# ATS.net
KiCad netlist of a schematic drawn in EAGLE
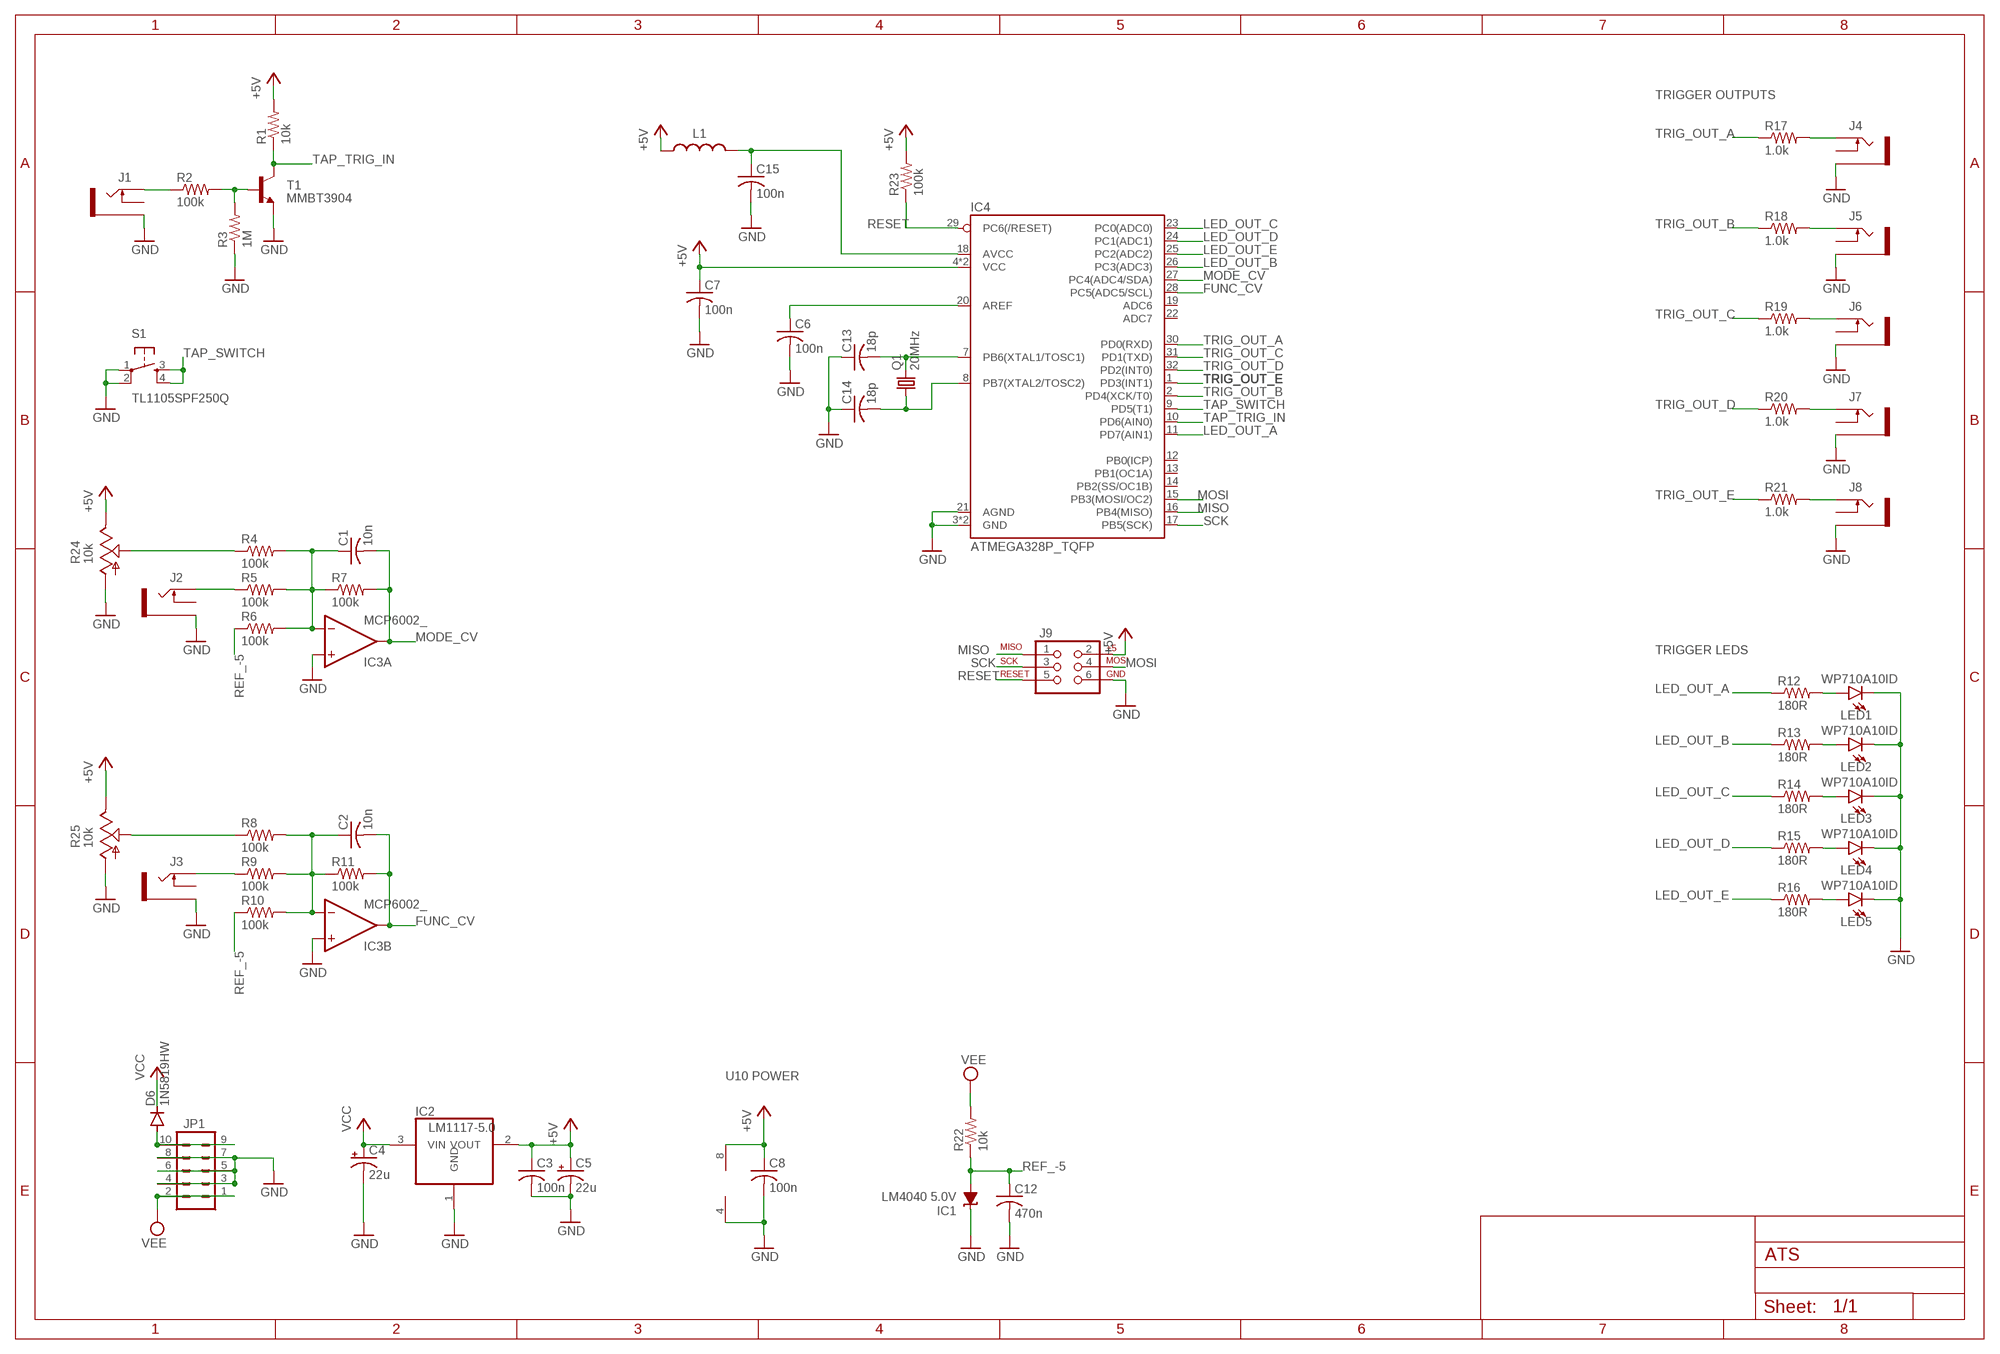
[diagram p0: schematic, sheet 1]

(export (version "E")
  (design (tool "Eeschema 10.0.6"))
  (components
    (comp (ref "C1")
      (value "10n")
      (footprint "eagle-import:C0603")
      (libsource (lib "eagle-import") (part "C-USC0603"))
    )
    (comp (ref "C2")
      (value "10n")
      (footprint "eagle-import:C0603")
      (libsource (lib "eagle-import") (part "C-USC0603"))
    )
    (comp (ref "C3")
      (value "100n")
      (footprint "eagle-import:C0603")
      (libsource (lib "eagle-import") (part "C-USC0603"))
    )
    (comp (ref "C4")
      (value "22u")
      (footprint "eagle-import:PANASONIC_C")
      (libsource (lib "eagle-import") (part "CPOL-USC"))
    )
    (comp (ref "C5")
      (value "22u")
      (footprint "eagle-import:PANASONIC_C")
      (libsource (lib "eagle-import") (part "CPOL-USC"))
    )
    (comp (ref "C6")
      (value "100n")
      (footprint "eagle-import:C0603")
      (libsource (lib "eagle-import") (part "C-USC0603"))
    )
    (comp (ref "C7")
      (value "100n")
      (footprint "eagle-import:C0603")
      (libsource (lib "eagle-import") (part "C-USC0603"))
    )
    (comp (ref "C8")
      (value "100n")
      (footprint "eagle-import:C0603")
      (libsource (lib "eagle-import") (part "C-USC0603"))
    )
    (comp (ref "C12")
      (value "470n")
      (footprint "eagle-import:C0603")
      (libsource (lib "eagle-import") (part "C-USC0603"))
    )
    (comp (ref "C13")
      (value "18p")
      (footprint "eagle-import:C0603")
      (libsource (lib "eagle-import") (part "C-USC0603"))
    )
    (comp (ref "C14")
      (value "18p")
      (footprint "eagle-import:C0603")
      (libsource (lib "eagle-import") (part "C-USC0603"))
    )
    (comp (ref "C15")
      (value "100n")
      (footprint "eagle-import:C0603")
      (libsource (lib "eagle-import") (part "C-USC0603"))
    )
    (comp (ref "D6")
      (value "1N5819HW")
      (footprint "eagle-import:SOD123")
      (libsource (lib "eagle-import") (part "DIODE-SOD123"))
    )
    (comp (ref "IC1")
      (value "LM4040 5.0V")
      (footprint "eagle-import:DBZ_R-PDSO-G3")
      (fields (field (name "MF") "TEXAS INSTRUMENT CONNECTORS") (field (name "MPN") "LM4041C12QDBZT"))
      (libsource (lib "eagle-import") (part "LM4041DBZC12"))
    )
    (comp (ref "IC2")
      (value "LM1117-5.0")
      (footprint "eagle-import:SOT223")
      (fields (field (name "MPN") "REG1117"))
      (libsource (lib "eagle-import") (part "REG1117"))
    )
    (comp (ref "IC3")
      (value "MCP6002_")
      (footprint "eagle-import:SO08")
      (libsource (lib "eagle-import") (part "MCP6002_"))
    )
    (comp (ref "IC4")
      (value "ATMEGA328P_TQFP")
      (footprint "eagle-import:TQFP32-08")
      (libsource (lib "eagle-import") (part "ATMEGA328P_TQFP"))
    )
    (comp (ref "J1")
      (value "THONKICONNNEW")
      (footprint "eagle-import:WQP-PJ301M-12_JACK")
      (libsource (lib "eagle-import") (part "THONKICONNNEW"))
    )
    (comp (ref "J2")
      (value "THONKICONNNEW")
      (footprint "eagle-import:WQP-PJ301M-12_JACK")
      (libsource (lib "eagle-import") (part "THONKICONNNEW"))
    )
    (comp (ref "J3")
      (value "THONKICONNNEW")
      (footprint "eagle-import:WQP-PJ301M-12_JACK")
      (libsource (lib "eagle-import") (part "THONKICONNNEW"))
    )
    (comp (ref "J4")
      (value "THONKICONNNEW")
      (footprint "eagle-import:WQP-PJ301M-12_JACK")
      (libsource (lib "eagle-import") (part "THONKICONNNEW"))
    )
    (comp (ref "J5")
      (value "THONKICONNNEW")
      (footprint "eagle-import:WQP-PJ301M-12_JACK")
      (libsource (lib "eagle-import") (part "THONKICONNNEW"))
    )
    (comp (ref "J6")
      (value "THONKICONNNEW")
      (footprint "eagle-import:WQP-PJ301M-12_JACK")
      (libsource (lib "eagle-import") (part "THONKICONNNEW"))
    )
    (comp (ref "J7")
      (value "THONKICONNNEW")
      (footprint "eagle-import:WQP-PJ301M-12_JACK")
      (libsource (lib "eagle-import") (part "THONKICONNNEW"))
    )
    (comp (ref "J8")
      (value "THONKICONNNEW")
      (footprint "eagle-import:WQP-PJ301M-12_JACK")
      (libsource (lib "eagle-import") (part "THONKICONNNEW"))
    )
    (comp (ref "J9")
      (value "AVR_SPI_PRG_6PTH")
      (footprint "eagle-import:2X3")
      (libsource (lib "eagle-import") (part "AVR_SPI_PRG_6PTH"))
    )
    (comp (ref "JP1")
      (value "EURO_POWER_HEADERREGULAR")
      (footprint "eagle-import:EURO_POWER_HEADER")
      (libsource (lib "eagle-import") (part "EURO_POWER_HEADERREGULAR"))
    )
    (comp (ref "L1")
      (value "470Ohm@100MHz")
      (footprint "eagle-import:WE-CBF_0603(W=2.2)")
      (libsource (lib "eagle-import") (part "WE-CBF_0603_WB_HS_742792642"))
    )
    (comp (ref "LED1")
      (value "WP710A10ID")
      (footprint "eagle-import:LED_3MM")
      (fields (field (name "SPICEPREFIX") "D"))
      (libsource (lib "eagle-import") (part "LED3MM"))
    )
    (comp (ref "LED2")
      (value "WP710A10ID")
      (footprint "eagle-import:LED_3MM")
      (libsource (lib "eagle-import") (part "LED3MM"))
    )
    (comp (ref "LED3")
      (value "WP710A10ID")
      (footprint "eagle-import:LED_3MM")
      (libsource (lib "eagle-import") (part "LED3MM"))
    )
    (comp (ref "LED4")
      (value "WP710A10ID")
      (footprint "eagle-import:LED_3MM")
      (libsource (lib "eagle-import") (part "LED3MM"))
    )
    (comp (ref "LED5")
      (value "WP710A10ID")
      (footprint "eagle-import:LED_3MM")
      (libsource (lib "eagle-import") (part "LED3MM"))
    )
    (comp (ref "Q1")
      (value "20MHz")
      (footprint "eagle-import:HC49UP")
      (libsource (lib "eagle-import") (part "CRYSTALHC49UP"))
    )
    (comp (ref "R1")
      (value "10k")
      (footprint "eagle-import:R0603")
      (libsource (lib "eagle-import") (part "R-US_R0603"))
    )
    (comp (ref "R2")
      (value "100k")
      (footprint "eagle-import:R0603")
      (libsource (lib "eagle-import") (part "R-US_R0603"))
    )
    (comp (ref "R3")
      (value "1M")
      (footprint "eagle-import:R0603")
      (libsource (lib "eagle-import") (part "R-US_R0603"))
    )
    (comp (ref "R4")
      (value "100k")
      (footprint "eagle-import:R0603")
      (libsource (lib "eagle-import") (part "R-US_R0603"))
    )
    (comp (ref "R5")
      (value "100k")
      (footprint "eagle-import:R0603")
      (libsource (lib "eagle-import") (part "R-US_R0603"))
    )
    (comp (ref "R6")
      (value "100k")
      (footprint "eagle-import:R0603")
      (libsource (lib "eagle-import") (part "R-US_R0603"))
    )
    (comp (ref "R7")
      (value "100k")
      (footprint "eagle-import:R0603")
      (libsource (lib "eagle-import") (part "R-US_R0603"))
    )
    (comp (ref "R8")
      (value "100k")
      (footprint "eagle-import:R0603")
      (libsource (lib "eagle-import") (part "R-US_R0603"))
    )
    (comp (ref "R9")
      (value "100k")
      (footprint "eagle-import:R0603")
      (libsource (lib "eagle-import") (part "R-US_R0603"))
    )
    (comp (ref "R10")
      (value "100k")
      (footprint "eagle-import:R0603")
      (libsource (lib "eagle-import") (part "R-US_R0603"))
    )
    (comp (ref "R11")
      (value "100k")
      (footprint "eagle-import:R0603")
      (libsource (lib "eagle-import") (part "R-US_R0603"))
    )
    (comp (ref "R12")
      (value "180R")
      (footprint "eagle-import:R0603")
      (libsource (lib "eagle-import") (part "R-US_R0603"))
    )
    (comp (ref "R13")
      (value "180R")
      (footprint "eagle-import:R0603")
      (libsource (lib "eagle-import") (part "R-US_R0603"))
    )
    (comp (ref "R14")
      (value "180R")
      (footprint "eagle-import:R0603")
      (libsource (lib "eagle-import") (part "R-US_R0603"))
    )
    (comp (ref "R15")
      (value "180R")
      (footprint "eagle-import:R0603")
      (libsource (lib "eagle-import") (part "R-US_R0603"))
    )
    (comp (ref "R16")
      (value "180R")
      (footprint "eagle-import:R0603")
      (libsource (lib "eagle-import") (part "R-US_R0603"))
    )
    (comp (ref "R17")
      (value "1.0k")
      (footprint "eagle-import:R0603")
      (libsource (lib "eagle-import") (part "R-US_R0603"))
    )
    (comp (ref "R18")
      (value "1.0k")
      (footprint "eagle-import:R0603")
      (libsource (lib "eagle-import") (part "R-US_R0603"))
    )
    (comp (ref "R19")
      (value "1.0k")
      (footprint "eagle-import:R0603")
      (libsource (lib "eagle-import") (part "R-US_R0603"))
    )
    (comp (ref "R20")
      (value "1.0k")
      (footprint "eagle-import:R0603")
      (libsource (lib "eagle-import") (part "R-US_R0603"))
    )
    (comp (ref "R21")
      (value "1.0k")
      (footprint "eagle-import:R0603")
      (libsource (lib "eagle-import") (part "R-US_R0603"))
    )
    (comp (ref "R22")
      (value "10k")
      (footprint "eagle-import:R0603")
      (libsource (lib "eagle-import") (part "R-US_R0603"))
    )
    (comp (ref "R23")
      (value "100k")
      (footprint "eagle-import:R0603")
      (libsource (lib "eagle-import") (part "R-US_R0603"))
    )
    (comp (ref "R24")
      (value "10k")
      (footprint "eagle-import:9MM_SNAP-IN_POT")
      (libsource (lib "eagle-import") (part "9MM_SNAP-IN_POT_"))
    )
    (comp (ref "R25")
      (value "10k")
      (footprint "eagle-import:9MM_SNAP-IN_POT")
      (libsource (lib "eagle-import") (part "9MM_SNAP-IN_POT_"))
    )
    (comp (ref "S1")
      (value "TL1105SPF250Q")
      (footprint "eagle-import:TACTILE-PTH")
      (libsource (lib "eagle-import") (part "TAC_SWITCHPTH"))
    )
    (comp (ref "T1")
      (value "MMBT3904")
      (footprint "eagle-import:SOT23-BEC")
      (libsource (lib "eagle-import") (part "-NPN-SOT23-BECMMBT3904LT1"))
    )
  )
  (nets
    (net (code "1") (name "+5V") (class "Default")
      (node (ref "C3") (pin "1") (pinfunction "1_1") (pintype "passive"))
      (node (ref "C5") (pin "+") (pinfunction "+_+") (pintype "passive"))
      (node (ref "C7") (pin "1") (pinfunction "1_1") (pintype "passive"))
      (node (ref "C8") (pin "1") (pinfunction "1_1") (pintype "passive"))
      (node (ref "IC2") (pin "2") (pinfunction "VOUT_2") (pintype "output"))
      (node (ref "IC3") (pin "8") (pinfunction "V+_8") (pintype "power_in"))
      (node (ref "IC4") (pin "4") (pinfunction "VCC_4") (pintype "bidirectional"))
      (node (ref "IC4") (pin "6") (pinfunction "VCC_6") (pintype "bidirectional"))
      (node (ref "J9") (pin "2") (pinfunction "2_2") (pintype "passive"))
      (node (ref "L1") (pin "1") (pinfunction "1_1") (pintype "passive"))
      (node (ref "R1") (pin "2") (pinfunction "2_2") (pintype "passive"))
      (node (ref "R23") (pin "2") (pinfunction "2_2") (pintype "passive"))
      (node (ref "R24") (pin "3") (pinfunction "E_3") (pintype "passive"))
      (node (ref "R25") (pin "3") (pinfunction "E_3") (pintype "passive"))
    )
    (net (code "2") (name "/FUNC_CV") (class "Default")
      (node (ref "C2") (pin "2") (pinfunction "2_2") (pintype "passive"))
      (node (ref "IC3") (pin "7") (pinfunction "OUT_7") (pintype "output"))
      (node (ref "IC4") (pin "28") (pinfunction "PC5(ADC5/SCL)_28") (pintype "bidirectional"))
      (node (ref "R11") (pin "2") (pinfunction "2_2") (pintype "passive"))
    )
    (net (code "3") (name "/LED_OUT_A") (class "Default")
      (node (ref "IC4") (pin "11") (pinfunction "PD7(AIN1)_11") (pintype "bidirectional"))
      (node (ref "R12") (pin "1") (pinfunction "1_1") (pintype "passive"))
    )
    (net (code "4") (name "/LED_OUT_B") (class "Default")
      (node (ref "IC4") (pin "26") (pinfunction "PC3(ADC3)_26") (pintype "bidirectional"))
      (node (ref "R13") (pin "1") (pinfunction "1_1") (pintype "passive"))
    )
    (net (code "5") (name "/LED_OUT_C") (class "Default")
      (node (ref "IC4") (pin "23") (pinfunction "PC0(ADC0)_23") (pintype "bidirectional"))
      (node (ref "R14") (pin "1") (pinfunction "1_1") (pintype "passive"))
    )
    (net (code "6") (name "/LED_OUT_D") (class "Default")
      (node (ref "IC4") (pin "24") (pinfunction "PC1(ADC1)_24") (pintype "bidirectional"))
      (node (ref "R15") (pin "1") (pinfunction "1_1") (pintype "passive"))
    )
    (net (code "7") (name "/LED_OUT_E") (class "Default")
      (node (ref "IC4") (pin "25") (pinfunction "PC2(ADC2)_25") (pintype "bidirectional"))
      (node (ref "R16") (pin "1") (pinfunction "1_1") (pintype "passive"))
    )
    (net (code "8") (name "/MISO") (class "Default")
      (node (ref "IC4") (pin "16") (pinfunction "PB4(MISO)_16") (pintype "bidirectional"))
      (node (ref "J9") (pin "1") (pinfunction "1_1") (pintype "passive"))
    )
    (net (code "9") (name "/MODE_CV") (class "Default")
      (node (ref "C1") (pin "2") (pinfunction "2_2") (pintype "passive"))
      (node (ref "IC3") (pin "1") (pinfunction "OUT_1") (pintype "output"))
      (node (ref "IC4") (pin "27") (pinfunction "PC4(ADC4/SDA)_27") (pintype "bidirectional"))
      (node (ref "R7") (pin "2") (pinfunction "2_2") (pintype "passive"))
    )
    (net (code "10") (name "/MOSI") (class "Default")
      (node (ref "IC4") (pin "15") (pinfunction "PB3(MOSI/OC2)_15") (pintype "bidirectional"))
      (node (ref "J9") (pin "4") (pinfunction "4_4") (pintype "passive"))
    )
    (net (code "11") (name "/REF_-5") (class "Default")
      (node (ref "C12") (pin "1") (pinfunction "1_1") (pintype "passive"))
      (node (ref "IC1") (pin "2") (pinfunction "A_2") (pintype "passive"))
      (node (ref "R10") (pin "1") (pinfunction "1_1") (pintype "passive"))
      (node (ref "R22") (pin "1") (pinfunction "1_1") (pintype "passive"))
      (node (ref "R6") (pin "1") (pinfunction "1_1") (pintype "passive"))
    )
    (net (code "12") (name "/RESET") (class "Default")
      (node (ref "IC4") (pin "29") (pinfunction "PC6(/RESET)_29") (pintype "bidirectional"))
      (node (ref "J9") (pin "5") (pinfunction "5_5") (pintype "passive"))
      (node (ref "R23") (pin "1") (pinfunction "1_1") (pintype "passive"))
    )
    (net (code "13") (name "/SCK") (class "Default")
      (node (ref "IC4") (pin "17") (pinfunction "PB5(SCK)_17") (pintype "bidirectional"))
      (node (ref "J9") (pin "3") (pinfunction "3_3") (pintype "passive"))
    )
    (net (code "14") (name "/TAP_SWITCH") (class "Default")
      (node (ref "IC4") (pin "9") (pinfunction "PD5(T1)_9") (pintype "bidirectional"))
      (node (ref "S1") (pin "3") (pinfunction "3_3") (pintype "passive"))
      (node (ref "S1") (pin "4") (pinfunction "4_4") (pintype "passive"))
    )
    (net (code "15") (name "/TAP_TRIG_IN") (class "Default")
      (node (ref "IC4") (pin "10") (pinfunction "PD6(AIN0)_10") (pintype "bidirectional"))
      (node (ref "R1") (pin "1") (pinfunction "1_1") (pintype "passive"))
      (node (ref "T1") (pin "C") (pinfunction "C_C") (pintype "passive"))
    )
    (net (code "16") (name "/TRIG_OUT_A") (class "Default")
      (node (ref "IC4") (pin "30") (pinfunction "PD0(RXD)_30") (pintype "bidirectional"))
      (node (ref "R17") (pin "1") (pinfunction "1_1") (pintype "passive"))
    )
    (net (code "17") (name "/TRIG_OUT_B") (class "Default")
      (node (ref "IC4") (pin "2") (pinfunction "PD4(XCK/T0)_2") (pintype "bidirectional"))
      (node (ref "R18") (pin "1") (pinfunction "1_1") (pintype "passive"))
    )
    (net (code "18") (name "/TRIG_OUT_C") (class "Default")
      (node (ref "IC4") (pin "31") (pinfunction "PD1(TXD)_31") (pintype "bidirectional"))
      (node (ref "R19") (pin "1") (pinfunction "1_1") (pintype "passive"))
    )
    (net (code "19") (name "/TRIG_OUT_D") (class "Default")
      (node (ref "IC4") (pin "32") (pinfunction "PD2(INT0)_32") (pintype "bidirectional"))
      (node (ref "R20") (pin "1") (pinfunction "1_1") (pintype "passive"))
    )
    (net (code "20") (name "/TRIG_OUT_E") (class "Default")
      (node (ref "IC4") (pin "1") (pinfunction "PD3(INT1)_1") (pintype "bidirectional"))
      (node (ref "R21") (pin "1") (pinfunction "1_1") (pintype "passive"))
    )
    (net (code "21") (name "GND") (class "Default")
      (node (ref "C12") (pin "2") (pinfunction "2_2") (pintype "passive"))
      (node (ref "C13") (pin "1") (pinfunction "1_1") (pintype "passive"))
      (node (ref "C14") (pin "1") (pinfunction "1_1") (pintype "passive"))
      (node (ref "C15") (pin "2") (pinfunction "2_2") (pintype "passive"))
      (node (ref "C3") (pin "2") (pinfunction "2_2") (pintype "passive"))
      (node (ref "C4") (pin "-") (pinfunction "-_-") (pintype "passive"))
      (node (ref "C5") (pin "-") (pinfunction "-_-") (pintype "passive"))
      (node (ref "C6") (pin "2") (pinfunction "2_2") (pintype "passive"))
      (node (ref "C7") (pin "2") (pinfunction "2_2") (pintype "passive"))
      (node (ref "C8") (pin "2") (pinfunction "2_2") (pintype "passive"))
      (node (ref "IC1") (pin "1") (pinfunction "C_1") (pintype "passive"))
      (node (ref "IC2") (pin "1") (pinfunction "GND_1") (pintype "power_in"))
      (node (ref "IC3") (pin "3") (pinfunction "+IN_3") (pintype "input"))
      (node (ref "IC3") (pin "4") (pinfunction "V-_4") (pintype "power_in"))
      (node (ref "IC3") (pin "5") (pinfunction "+IN_5") (pintype "input"))
      (node (ref "IC4") (pin "21") (pinfunction "AGND_21") (pintype "bidirectional"))
      (node (ref "IC4") (pin "3") (pinfunction "GND_3") (pintype "bidirectional"))
      (node (ref "IC4") (pin "5") (pinfunction "GND_5") (pintype "bidirectional"))
      (node (ref "J1") (pin "P$3_SLEEVE") (pinfunction "SLEEVE_P$3_SLEEVE") (pintype "passive"))
      (node (ref "J2") (pin "P$3_SLEEVE") (pinfunction "SLEEVE_P$3_SLEEVE") (pintype "passive"))
      (node (ref "J3") (pin "P$3_SLEEVE") (pinfunction "SLEEVE_P$3_SLEEVE") (pintype "passive"))
      (node (ref "J4") (pin "P$3_SLEEVE") (pinfunction "SLEEVE_P$3_SLEEVE") (pintype "passive"))
      (node (ref "J5") (pin "P$3_SLEEVE") (pinfunction "SLEEVE_P$3_SLEEVE") (pintype "passive"))
      (node (ref "J6") (pin "P$3_SLEEVE") (pinfunction "SLEEVE_P$3_SLEEVE") (pintype "passive"))
      (node (ref "J7") (pin "P$3_SLEEVE") (pinfunction "SLEEVE_P$3_SLEEVE") (pintype "passive"))
      (node (ref "J8") (pin "P$3_SLEEVE") (pinfunction "SLEEVE_P$3_SLEEVE") (pintype "passive"))
      (node (ref "J9") (pin "6") (pinfunction "6_6") (pintype "passive"))
      (node (ref "JP1") (pin "3") (pinfunction "3_3") (pintype "passive"))
      (node (ref "JP1") (pin "4") (pinfunction "4_4") (pintype "passive"))
      (node (ref "JP1") (pin "5") (pinfunction "5_5") (pintype "passive"))
      (node (ref "JP1") (pin "6") (pinfunction "6_6") (pintype "passive"))
      (node (ref "JP1") (pin "7") (pinfunction "7_7") (pintype "passive"))
      (node (ref "JP1") (pin "8") (pinfunction "8_8") (pintype "passive"))
      (node (ref "LED1") (pin "K") (pinfunction "C_K") (pintype "passive"))
      (node (ref "LED2") (pin "K") (pinfunction "C_K") (pintype "passive"))
      (node (ref "LED3") (pin "K") (pinfunction "C_K") (pintype "passive"))
      (node (ref "LED4") (pin "K") (pinfunction "C_K") (pintype "passive"))
      (node (ref "LED5") (pin "K") (pinfunction "C_K") (pintype "passive"))
      (node (ref "R24") (pin "1") (pinfunction "A_1") (pintype "passive"))
      (node (ref "R25") (pin "1") (pinfunction "A_1") (pintype "passive"))
      (node (ref "R3") (pin "1") (pinfunction "1_1") (pintype "passive"))
      (node (ref "S1") (pin "1") (pinfunction "1_1") (pintype "passive"))
      (node (ref "S1") (pin "2") (pinfunction "2_2") (pintype "passive"))
      (node (ref "T1") (pin "E") (pinfunction "E_E") (pintype "passive"))
    )
    (net (code "22") (name "Net-(D6-PadA)") (class "Default")
      (node (ref "D6") (pin "A") (pinfunction "A_A") (pintype "passive"))
      (node (ref "JP1") (pin "10") (pinfunction "10_10") (pintype "passive"))
      (node (ref "JP1") (pin "9") (pinfunction "9_9") (pintype "passive"))
    )
    (net (code "23") (name "Net-(IC3A--IN)") (class "Default")
      (node (ref "C1") (pin "1") (pinfunction "1_1") (pintype "passive"))
      (node (ref "IC3") (pin "2") (pinfunction "-IN_2") (pintype "input"))
      (node (ref "R4") (pin "2") (pinfunction "2_2") (pintype "passive"))
      (node (ref "R5") (pin "2") (pinfunction "2_2") (pintype "passive"))
      (node (ref "R6") (pin "2") (pinfunction "2_2") (pintype "passive"))
      (node (ref "R7") (pin "1") (pinfunction "1_1") (pintype "passive"))
    )
    (net (code "24") (name "Net-(IC3B--IN)") (class "Default")
      (node (ref "C2") (pin "1") (pinfunction "1_1") (pintype "passive"))
      (node (ref "IC3") (pin "6") (pinfunction "-IN_6") (pintype "input"))
      (node (ref "R10") (pin "2") (pinfunction "2_2") (pintype "passive"))
      (node (ref "R11") (pin "1") (pinfunction "1_1") (pintype "passive"))
      (node (ref "R8") (pin "2") (pinfunction "2_2") (pintype "passive"))
      (node (ref "R9") (pin "2") (pinfunction "2_2") (pintype "passive"))
    )
    (net (code "25") (name "Net-(IC4-AREF)") (class "Default")
      (node (ref "C6") (pin "1") (pinfunction "1_1") (pintype "passive"))
      (node (ref "IC4") (pin "20") (pinfunction "AREF_20") (pintype "bidirectional"))
    )
    (net (code "26") (name "Net-(IC4-AVCC)") (class "Default")
      (node (ref "C15") (pin "1") (pinfunction "1_1") (pintype "passive"))
      (node (ref "IC4") (pin "18") (pinfunction "AVCC_18") (pintype "bidirectional"))
      (node (ref "L1") (pin "2") (pinfunction "2_2") (pintype "passive"))
    )
    (net (code "27") (name "Net-(IC4-PB6(XTAL1{slash}TOSC1))") (class "Default")
      (node (ref "C13") (pin "2") (pinfunction "2_2") (pintype "passive"))
      (node (ref "IC4") (pin "7") (pinfunction "PB6(XTAL1/TOSC1)_7") (pintype "bidirectional"))
      (node (ref "Q1") (pin "2") (pinfunction "2_2") (pintype "passive"))
    )
    (net (code "28") (name "Net-(IC4-PB7(XTAL2{slash}TOSC2))") (class "Default")
      (node (ref "C14") (pin "2") (pinfunction "2_2") (pintype "passive"))
      (node (ref "IC4") (pin "8") (pinfunction "PB7(XTAL2/TOSC2)_8") (pintype "bidirectional"))
      (node (ref "Q1") (pin "1") (pinfunction "1_1") (pintype "passive"))
    )
    (net (code "29") (name "Net-(J1-TIP)") (class "Default")
      (node (ref "J1") (pin "P$1_TIP") (pinfunction "TIP_P$1_TIP") (pintype "passive"))
      (node (ref "R2") (pin "1") (pinfunction "1_1") (pintype "passive"))
    )
    (net (code "30") (name "Net-(J2-TIP)") (class "Default")
      (node (ref "J2") (pin "P$1_TIP") (pinfunction "TIP_P$1_TIP") (pintype "passive"))
      (node (ref "R5") (pin "1") (pinfunction "1_1") (pintype "passive"))
    )
    (net (code "31") (name "Net-(J3-TIP)") (class "Default")
      (node (ref "J3") (pin "P$1_TIP") (pinfunction "TIP_P$1_TIP") (pintype "passive"))
      (node (ref "R9") (pin "1") (pinfunction "1_1") (pintype "passive"))
    )
    (net (code "32") (name "Net-(J4-TIP)") (class "Default")
      (node (ref "J4") (pin "P$1_TIP") (pinfunction "TIP_P$1_TIP") (pintype "passive"))
      (node (ref "R17") (pin "2") (pinfunction "2_2") (pintype "passive"))
    )
    (net (code "33") (name "Net-(J5-TIP)") (class "Default")
      (node (ref "J5") (pin "P$1_TIP") (pinfunction "TIP_P$1_TIP") (pintype "passive"))
      (node (ref "R18") (pin "2") (pinfunction "2_2") (pintype "passive"))
    )
    (net (code "34") (name "Net-(J6-TIP)") (class "Default")
      (node (ref "J6") (pin "P$1_TIP") (pinfunction "TIP_P$1_TIP") (pintype "passive"))
      (node (ref "R19") (pin "2") (pinfunction "2_2") (pintype "passive"))
    )
    (net (code "35") (name "Net-(J7-TIP)") (class "Default")
      (node (ref "J7") (pin "P$1_TIP") (pinfunction "TIP_P$1_TIP") (pintype "passive"))
      (node (ref "R20") (pin "2") (pinfunction "2_2") (pintype "passive"))
    )
    (net (code "36") (name "Net-(J8-TIP)") (class "Default")
      (node (ref "J8") (pin "P$1_TIP") (pinfunction "TIP_P$1_TIP") (pintype "passive"))
      (node (ref "R21") (pin "2") (pinfunction "2_2") (pintype "passive"))
    )
    (net (code "37") (name "Net-(LED1-PadA)") (class "Default")
      (node (ref "LED1") (pin "A") (pinfunction "A_A") (pintype "passive"))
      (node (ref "R12") (pin "2") (pinfunction "2_2") (pintype "passive"))
    )
    (net (code "38") (name "Net-(LED2-PadA)") (class "Default")
      (node (ref "LED2") (pin "A") (pinfunction "A_A") (pintype "passive"))
      (node (ref "R13") (pin "2") (pinfunction "2_2") (pintype "passive"))
    )
    (net (code "39") (name "Net-(LED3-PadA)") (class "Default")
      (node (ref "LED3") (pin "A") (pinfunction "A_A") (pintype "passive"))
      (node (ref "R14") (pin "2") (pinfunction "2_2") (pintype "passive"))
    )
    (net (code "40") (name "Net-(LED4-PadA)") (class "Default")
      (node (ref "LED4") (pin "A") (pinfunction "A_A") (pintype "passive"))
      (node (ref "R15") (pin "2") (pinfunction "2_2") (pintype "passive"))
    )
    (net (code "41") (name "Net-(LED5-PadA)") (class "Default")
      (node (ref "LED5") (pin "A") (pinfunction "A_A") (pintype "passive"))
      (node (ref "R16") (pin "2") (pinfunction "2_2") (pintype "passive"))
    )
    (net (code "42") (name "Net-(R2-Pad2)") (class "Default")
      (node (ref "R2") (pin "2") (pinfunction "2_2") (pintype "passive"))
      (node (ref "R3") (pin "2") (pinfunction "2_2") (pintype "passive"))
      (node (ref "T1") (pin "B") (pinfunction "B_B") (pintype "passive"))
    )
    (net (code "43") (name "Net-(R24-S)") (class "Default")
      (node (ref "R24") (pin "2") (pinfunction "S_2") (pintype "passive"))
      (node (ref "R4") (pin "1") (pinfunction "1_1") (pintype "passive"))
    )
    (net (code "44") (name "Net-(R25-S)") (class "Default")
      (node (ref "R25") (pin "2") (pinfunction "S_2") (pintype "passive"))
      (node (ref "R8") (pin "1") (pinfunction "1_1") (pintype "passive"))
    )
    (net (code "45") (name "VCC") (class "Default")
      (node (ref "C4") (pin "+") (pinfunction "+_+") (pintype "passive"))
      (node (ref "D6") (pin "C") (pinfunction "C_C") (pintype "passive"))
      (node (ref "IC2") (pin "3") (pinfunction "VIN_3") (pintype "input"))
    )
    (net (code "46") (name "VEE") (class "Default")
      (node (ref "JP1") (pin "1") (pinfunction "1_1") (pintype "passive"))
      (node (ref "JP1") (pin "2") (pinfunction "2_2") (pintype "passive"))
      (node (ref "R22") (pin "2") (pinfunction "2_2") (pintype "passive"))
    )
    (net (code "47") (name "unconnected-(IC4-ADC6-Pad19)") (class "Default")
      (node (ref "IC4") (pin "19") (pinfunction "ADC6_19") (pintype "bidirectional"))
    )
    (net (code "48") (name "unconnected-(IC4-ADC7-Pad22)") (class "Default")
      (node (ref "IC4") (pin "22") (pinfunction "ADC7_22") (pintype "bidirectional"))
    )
    (net (code "49") (name "unconnected-(IC4-PB0(ICP)-Pad12)") (class "Default")
      (node (ref "IC4") (pin "12") (pinfunction "PB0(ICP)_12") (pintype "bidirectional"))
    )
    (net (code "50") (name "unconnected-(IC4-PB1(OC1A)-Pad13)") (class "Default")
      (node (ref "IC4") (pin "13") (pinfunction "PB1(OC1A)_13") (pintype "bidirectional"))
    )
    (net (code "51") (name "unconnected-(IC4-PB2(SS{slash}OC1B)-Pad14)") (class "Default")
      (node (ref "IC4") (pin "14") (pinfunction "PB2(SS/OC1B)_14") (pintype "bidirectional"))
    )
    (net (code "52") (name "unconnected-(J1-SWITCH-PadP$2_SWITCH)") (class "Default")
      (node (ref "J1") (pin "P$2_SWITCH") (pinfunction "SWITCH_P$2_SWITCH") (pintype "passive"))
    )
    (net (code "53") (name "unconnected-(J2-SWITCH-PadP$2_SWITCH)") (class "Default")
      (node (ref "J2") (pin "P$2_SWITCH") (pinfunction "SWITCH_P$2_SWITCH") (pintype "passive"))
    )
    (net (code "54") (name "unconnected-(J3-SWITCH-PadP$2_SWITCH)") (class "Default")
      (node (ref "J3") (pin "P$2_SWITCH") (pinfunction "SWITCH_P$2_SWITCH") (pintype "passive"))
    )
    (net (code "55") (name "unconnected-(J4-SWITCH-PadP$2_SWITCH)") (class "Default")
      (node (ref "J4") (pin "P$2_SWITCH") (pinfunction "SWITCH_P$2_SWITCH") (pintype "passive"))
    )
    (net (code "56") (name "unconnected-(J5-SWITCH-PadP$2_SWITCH)") (class "Default")
      (node (ref "J5") (pin "P$2_SWITCH") (pinfunction "SWITCH_P$2_SWITCH") (pintype "passive"))
    )
    (net (code "57") (name "unconnected-(J6-SWITCH-PadP$2_SWITCH)") (class "Default")
      (node (ref "J6") (pin "P$2_SWITCH") (pinfunction "SWITCH_P$2_SWITCH") (pintype "passive"))
    )
    (net (code "58") (name "unconnected-(J7-SWITCH-PadP$2_SWITCH)") (class "Default")
      (node (ref "J7") (pin "P$2_SWITCH") (pinfunction "SWITCH_P$2_SWITCH") (pintype "passive"))
    )
    (net (code "59") (name "unconnected-(J8-SWITCH-PadP$2_SWITCH)") (class "Default")
      (node (ref "J8") (pin "P$2_SWITCH") (pinfunction "SWITCH_P$2_SWITCH") (pintype "passive"))
    )
  )
)
